# Swarm_Board_2.net
KiCad netlist of a schematic drawn in EAGLE
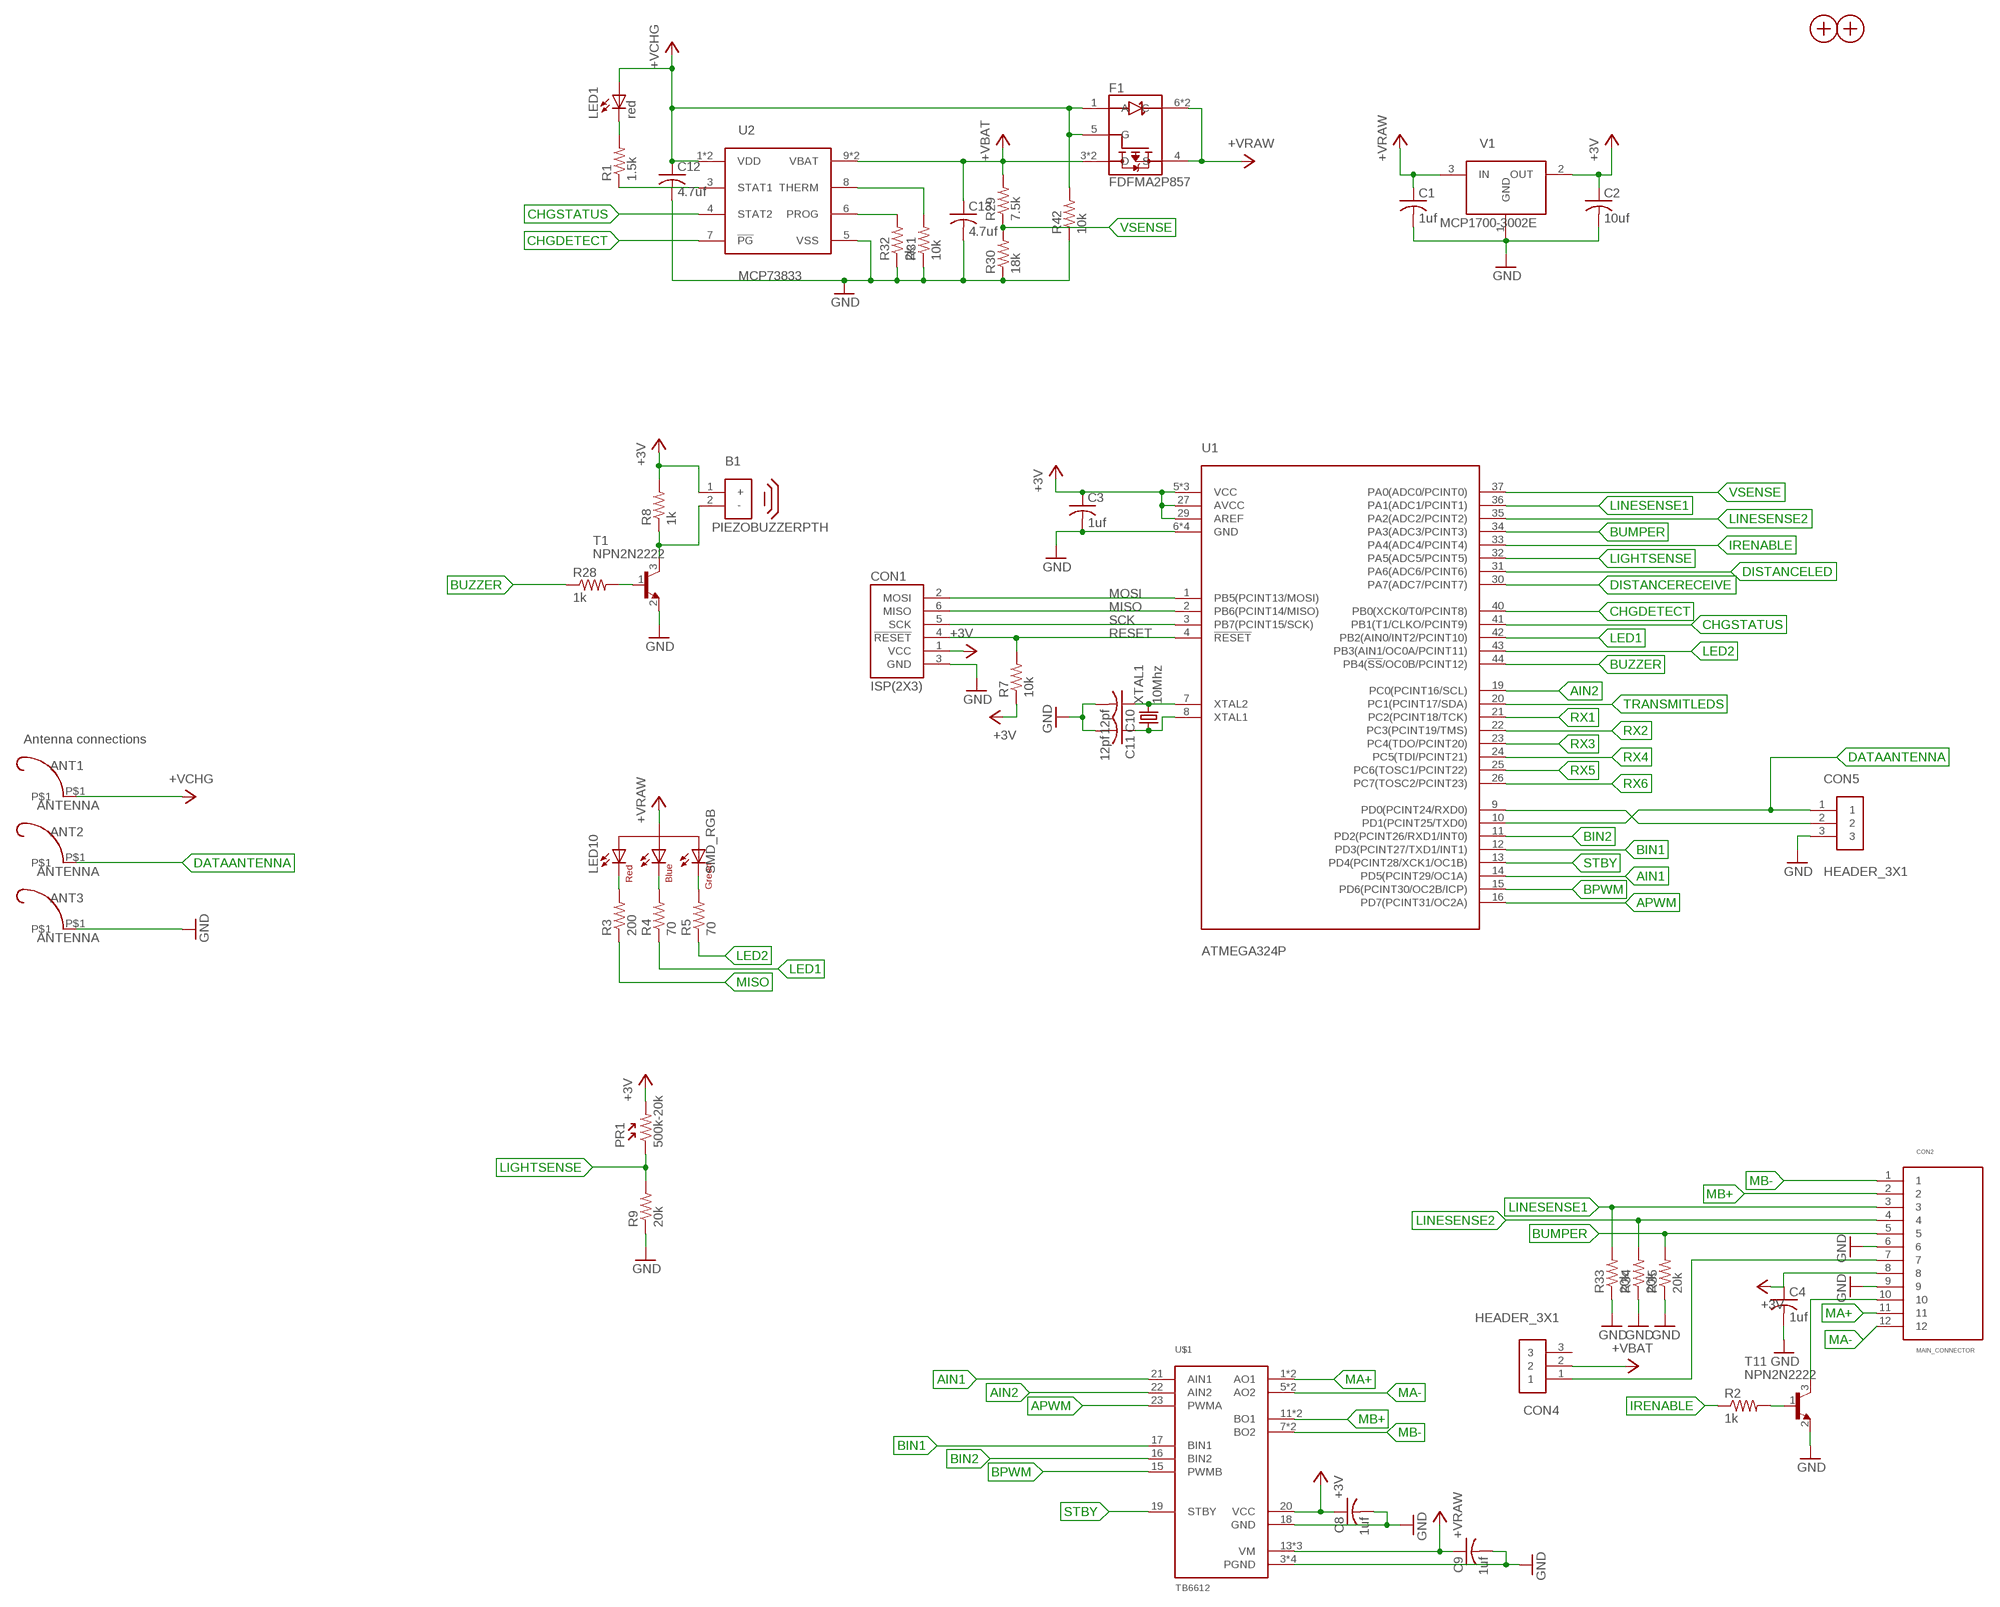
[diagram p0: schematic, sheet 1, part 1 of 2]
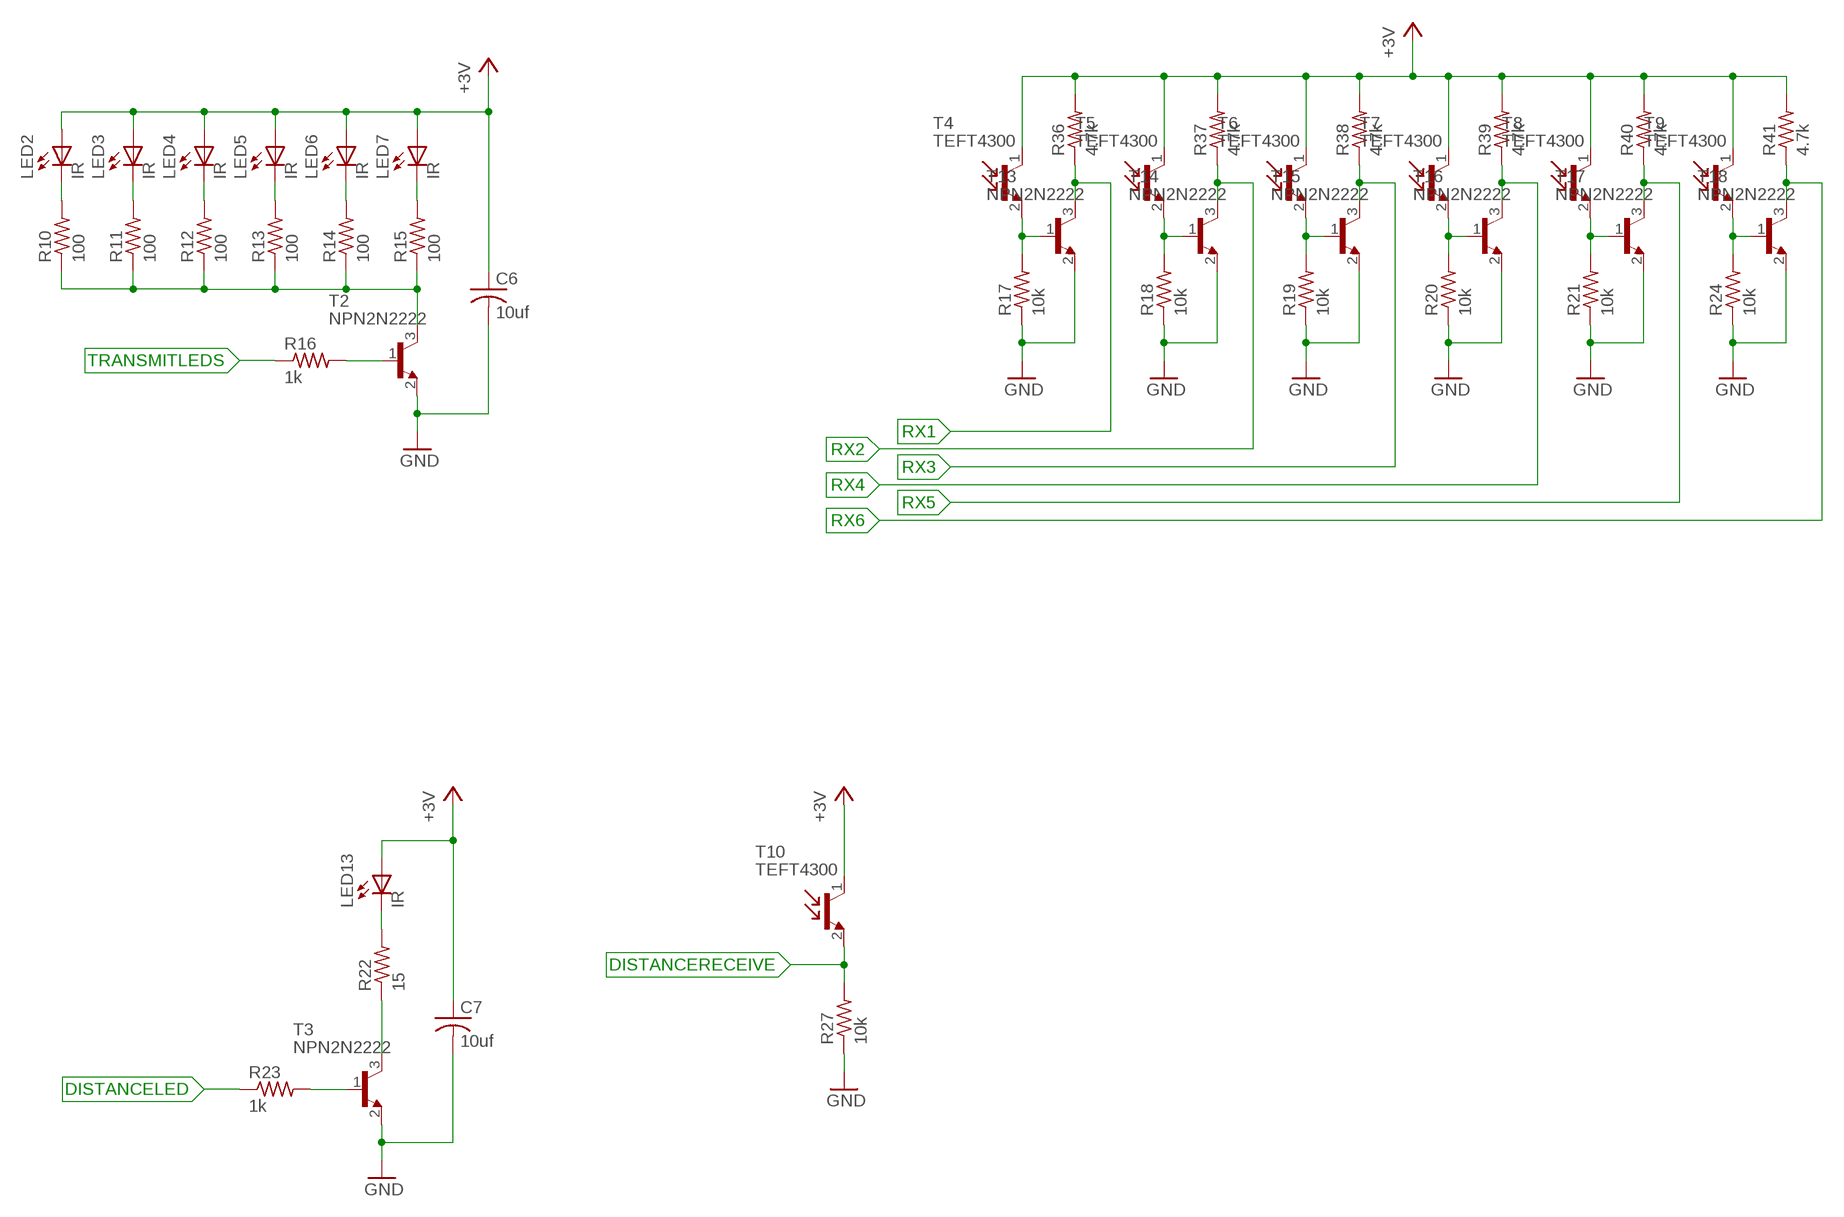
[diagram p1: schematic, sheet 1, part 2 of 2]

(export (version "E")
  (design (tool "Eeschema 10.0.6"))
  (components
    (comp (ref "ANT1")
      (value "ANTENNA")
      (footprint "eagle-import:ANTENNA")
      (libsource (lib "eagle-import") (part "ANTENNA"))
    )
    (comp (ref "ANT2")
      (value "ANTENNA")
      (footprint "eagle-import:ANTENNA")
      (libsource (lib "eagle-import") (part "ANTENNA"))
    )
    (comp (ref "ANT3")
      (value "ANTENNA")
      (footprint "eagle-import:ANTENNA")
      (libsource (lib "eagle-import") (part "ANTENNA"))
    )
    (comp (ref "B1")
      (value "PIEZOBUZZERPTH")
      (footprint "eagle-import:PIEZOBUZZER")
      (libsource (lib "eagle-import") (part "PIEZOBUZZERPTH"))
    )
    (comp (ref "C1")
      (value "1uf")
      (footprint "eagle-import:0603")
      (libsource (lib "eagle-import") (part "CAP0603"))
    )
    (comp (ref "C2")
      (value "10uf")
      (footprint "eagle-import:0805")
      (libsource (lib "eagle-import") (part "CAP0805"))
    )
    (comp (ref "C3")
      (value "1uf")
      (footprint "eagle-import:0603")
      (libsource (lib "eagle-import") (part "CAP0603"))
    )
    (comp (ref "C4")
      (value "1uf")
      (footprint "eagle-import:0603")
      (libsource (lib "eagle-import") (part "CAP0603"))
    )
    (comp (ref "C6")
      (value "10uf")
      (footprint "eagle-import:0805")
      (libsource (lib "eagle-import") (part "CAP0805"))
    )
    (comp (ref "C7")
      (value "10uf")
      (footprint "eagle-import:0805")
      (libsource (lib "eagle-import") (part "CAP0805"))
    )
    (comp (ref "C8")
      (value "1uf")
      (footprint "eagle-import:0603")
      (libsource (lib "eagle-import") (part "CAP0603"))
    )
    (comp (ref "C9")
      (value "1uf")
      (footprint "eagle-import:0603")
      (libsource (lib "eagle-import") (part "CAP0603"))
    )
    (comp (ref "C10")
      (value "12pf")
      (footprint "eagle-import:0603")
      (libsource (lib "eagle-import") (part "CAP0603"))
    )
    (comp (ref "C11")
      (value "12pf")
      (footprint "eagle-import:0603")
      (libsource (lib "eagle-import") (part "CAP0603"))
    )
    (comp (ref "C12")
      (value "4.7uf")
      (footprint "eagle-import:0603")
      (libsource (lib "eagle-import") (part "CAP0603"))
    )
    (comp (ref "C13")
      (value "4.7uf")
      (footprint "eagle-import:0603")
      (libsource (lib "eagle-import") (part "CAP0603"))
    )
    (comp (ref "CON1")
      (value "ISP(2X3)")
      (footprint "eagle-import:PINHEADER(2X3)")
      (libsource (lib "eagle-import") (part "ISP(2X3)"))
    )
    (comp (ref "CON2")
      (value "MAIN_CONNECTOR")
      (footprint "eagle-import:FEMALE_HEADER_2MM_2X6")
      (libsource (lib "eagle-import") (part "MAIN_CONNECTOR"))
    )
    (comp (ref "CON4")
      (value "HEADER_3X1")
      (footprint "eagle-import:3PINHEADER_.100_")
      (libsource (lib "eagle-import") (part "HEADER_3X1"))
    )
    (comp (ref "CON5")
      (value "HEADER_3X1")
      (footprint "eagle-import:3PINHEADER_.100_")
      (libsource (lib "eagle-import") (part "HEADER_3X1"))
    )
    (comp (ref "F1")
      (value "FDFMA2P857")
      (footprint "eagle-import:MICROFET2X2MM")
      (libsource (lib "eagle-import") (part "FDFMA2P857"))
    )
    (comp (ref "H1")
      (value "MOUNTINGHOLE")
      (footprint "eagle-import:MOUNTINGHOLE")
      (libsource (lib "eagle-import") (part "MOUNTINGHOLE"))
    )
    (comp (ref "H2")
      (value "MOUNTINGHOLE")
      (footprint "eagle-import:MOUNTINGHOLE")
      (libsource (lib "eagle-import") (part "MOUNTINGHOLE"))
    )
    (comp (ref "LED1")
      (value "red")
      (footprint "eagle-import:LED0603")
      (libsource (lib "eagle-import") (part "LED0603"))
    )
    (comp (ref "LED2")
      (value "IR")
      (footprint "eagle-import:5MM_LED_RA")
      (libsource (lib "eagle-import") (part "LED5MMRA"))
    )
    (comp (ref "LED3")
      (value "IR")
      (footprint "eagle-import:5MM_LED_RA")
      (libsource (lib "eagle-import") (part "LED5MMRA"))
    )
    (comp (ref "LED4")
      (value "IR")
      (footprint "eagle-import:5MM_LED_RA")
      (libsource (lib "eagle-import") (part "LED5MMRA"))
    )
    (comp (ref "LED5")
      (value "IR")
      (footprint "eagle-import:5MM_LED_RA")
      (libsource (lib "eagle-import") (part "LED5MMRA"))
    )
    (comp (ref "LED6")
      (value "IR")
      (footprint "eagle-import:5MM_LED_RA")
      (libsource (lib "eagle-import") (part "LED5MMRA"))
    )
    (comp (ref "LED7")
      (value "IR")
      (footprint "eagle-import:5MM_LED_RA")
      (libsource (lib "eagle-import") (part "LED5MMRA"))
    )
    (comp (ref "LED10")
      (value "SMD_RGB")
      (footprint "eagle-import:PLCC4")
      (libsource (lib "eagle-import") (part "SMD_RGB"))
    )
    (comp (ref "LED13")
      (value "IR")
      (footprint "eagle-import:5MM_LED_RA")
      (libsource (lib "eagle-import") (part "LED5MMRA"))
    )
    (comp (ref "PR1")
      (value "500k-20k")
      (footprint "eagle-import:CDSPHOTOCELL")
      (libsource (lib "eagle-import") (part "CDSPHOTORESISTOR"))
    )
    (comp (ref "R1")
      (value "1.5k")
      (footprint "eagle-import:0603")
      (libsource (lib "eagle-import") (part "RES0603"))
    )
    (comp (ref "R2")
      (value "1k")
      (footprint "eagle-import:0603")
      (libsource (lib "eagle-import") (part "RES0603"))
    )
    (comp (ref "R3")
      (value "200")
      (footprint "eagle-import:0603")
      (libsource (lib "eagle-import") (part "RES0603"))
    )
    (comp (ref "R4")
      (value "70")
      (footprint "eagle-import:0603")
      (libsource (lib "eagle-import") (part "RES0603"))
    )
    (comp (ref "R5")
      (value "70")
      (footprint "eagle-import:0603")
      (libsource (lib "eagle-import") (part "RES0603"))
    )
    (comp (ref "R7")
      (value "10k")
      (footprint "eagle-import:0603")
      (libsource (lib "eagle-import") (part "RES0603"))
    )
    (comp (ref "R8")
      (value "1k")
      (footprint "eagle-import:0603")
      (libsource (lib "eagle-import") (part "RES0603"))
    )
    (comp (ref "R9")
      (value "20k")
      (footprint "eagle-import:0603")
      (libsource (lib "eagle-import") (part "RES0603"))
    )
    (comp (ref "R10")
      (value "100")
      (footprint "eagle-import:0603")
      (libsource (lib "eagle-import") (part "RES0603"))
    )
    (comp (ref "R11")
      (value "100")
      (footprint "eagle-import:0603")
      (libsource (lib "eagle-import") (part "RES0603"))
    )
    (comp (ref "R12")
      (value "100")
      (footprint "eagle-import:0603")
      (libsource (lib "eagle-import") (part "RES0603"))
    )
    (comp (ref "R13")
      (value "100")
      (footprint "eagle-import:0603")
      (libsource (lib "eagle-import") (part "RES0603"))
    )
    (comp (ref "R14")
      (value "100")
      (footprint "eagle-import:0603")
      (libsource (lib "eagle-import") (part "RES0603"))
    )
    (comp (ref "R15")
      (value "100")
      (footprint "eagle-import:0603")
      (libsource (lib "eagle-import") (part "RES0603"))
    )
    (comp (ref "R16")
      (value "1k")
      (footprint "eagle-import:0603")
      (libsource (lib "eagle-import") (part "RES0603"))
    )
    (comp (ref "R17")
      (value "10k")
      (footprint "eagle-import:0603")
      (libsource (lib "eagle-import") (part "RES0603"))
    )
    (comp (ref "R18")
      (value "10k")
      (footprint "eagle-import:0603")
      (libsource (lib "eagle-import") (part "RES0603"))
    )
    (comp (ref "R19")
      (value "10k")
      (footprint "eagle-import:0603")
      (libsource (lib "eagle-import") (part "RES0603"))
    )
    (comp (ref "R20")
      (value "10k")
      (footprint "eagle-import:0603")
      (libsource (lib "eagle-import") (part "RES0603"))
    )
    (comp (ref "R21")
      (value "10k")
      (footprint "eagle-import:0603")
      (libsource (lib "eagle-import") (part "RES0603"))
    )
    (comp (ref "R22")
      (value "15")
      (footprint "eagle-import:0603")
      (libsource (lib "eagle-import") (part "RES0603"))
    )
    (comp (ref "R23")
      (value "1k")
      (footprint "eagle-import:0603")
      (libsource (lib "eagle-import") (part "RES0603"))
    )
    (comp (ref "R24")
      (value "10k")
      (footprint "eagle-import:0603")
      (libsource (lib "eagle-import") (part "RES0603"))
    )
    (comp (ref "R27")
      (value "10k")
      (footprint "eagle-import:0603")
      (libsource (lib "eagle-import") (part "RES0603"))
    )
    (comp (ref "R28")
      (value "1k")
      (footprint "eagle-import:0603")
      (libsource (lib "eagle-import") (part "RES0603"))
    )
    (comp (ref "R29")
      (value "7.5k")
      (footprint "eagle-import:0603")
      (libsource (lib "eagle-import") (part "RES0603"))
    )
    (comp (ref "R30")
      (value "18k")
      (footprint "eagle-import:0603")
      (libsource (lib "eagle-import") (part "RES0603"))
    )
    (comp (ref "R31")
      (value "10k")
      (footprint "eagle-import:0603")
      (libsource (lib "eagle-import") (part "RES0603"))
    )
    (comp (ref "R32")
      (value "2k")
      (footprint "eagle-import:0603")
      (libsource (lib "eagle-import") (part "RES0603"))
    )
    (comp (ref "R33")
      (value "20k")
      (footprint "eagle-import:0603")
      (libsource (lib "eagle-import") (part "RES0603"))
    )
    (comp (ref "R34")
      (value "20k")
      (footprint "eagle-import:0603")
      (libsource (lib "eagle-import") (part "RES0603"))
    )
    (comp (ref "R35")
      (value "20k")
      (footprint "eagle-import:0603")
      (libsource (lib "eagle-import") (part "RES0603"))
    )
    (comp (ref "R36")
      (value "4.7k")
      (footprint "eagle-import:0603")
      (libsource (lib "eagle-import") (part "RES0603"))
    )
    (comp (ref "R37")
      (value "4.7k")
      (footprint "eagle-import:0603")
      (libsource (lib "eagle-import") (part "RES0603"))
    )
    (comp (ref "R38")
      (value "4.7k")
      (footprint "eagle-import:0603")
      (libsource (lib "eagle-import") (part "RES0603"))
    )
    (comp (ref "R39")
      (value "4.7k")
      (footprint "eagle-import:0603")
      (libsource (lib "eagle-import") (part "RES0603"))
    )
    (comp (ref "R40")
      (value "4.7k")
      (footprint "eagle-import:0603")
      (libsource (lib "eagle-import") (part "RES0603"))
    )
    (comp (ref "R41")
      (value "4.7k")
      (footprint "eagle-import:0603")
      (libsource (lib "eagle-import") (part "RES0603"))
    )
    (comp (ref "R42")
      (value "10k")
      (footprint "eagle-import:0603")
      (libsource (lib "eagle-import") (part "RES0603"))
    )
    (comp (ref "T1")
      (value "NPN2N2222")
      (footprint "eagle-import:SOT23")
      (libsource (lib "eagle-import") (part "NPN2N2222"))
    )
    (comp (ref "T2")
      (value "NPN2N2222")
      (footprint "eagle-import:SOT23")
      (libsource (lib "eagle-import") (part "NPN2N2222"))
    )
    (comp (ref "T3")
      (value "NPN2N2222")
      (footprint "eagle-import:SOT23")
      (libsource (lib "eagle-import") (part "NPN2N2222"))
    )
    (comp (ref "T4")
      (value "TEFT4300")
      (footprint "eagle-import:3MM_LED_RA")
      (libsource (lib "eagle-import") (part "TEFT4300"))
    )
    (comp (ref "T5")
      (value "TEFT4300")
      (footprint "eagle-import:3MM_LED_RA")
      (libsource (lib "eagle-import") (part "TEFT4300"))
    )
    (comp (ref "T6")
      (value "TEFT4300")
      (footprint "eagle-import:3MM_LED_RA")
      (libsource (lib "eagle-import") (part "TEFT4300"))
    )
    (comp (ref "T7")
      (value "TEFT4300")
      (footprint "eagle-import:3MM_LED_RA")
      (libsource (lib "eagle-import") (part "TEFT4300"))
    )
    (comp (ref "T8")
      (value "TEFT4300")
      (footprint "eagle-import:3MM_LED_RA")
      (libsource (lib "eagle-import") (part "TEFT4300"))
    )
    (comp (ref "T9")
      (value "TEFT4300")
      (footprint "eagle-import:3MM_LED_RA")
      (libsource (lib "eagle-import") (part "TEFT4300"))
    )
    (comp (ref "T10")
      (value "TEFT4300")
      (footprint "eagle-import:3MM_LED_RA")
      (libsource (lib "eagle-import") (part "TEFT4300"))
    )
    (comp (ref "T11")
      (value "NPN2N2222")
      (footprint "eagle-import:SOT23")
      (libsource (lib "eagle-import") (part "NPN2N2222"))
    )
    (comp (ref "T13")
      (value "NPN2N2222")
      (footprint "eagle-import:SOT23")
      (libsource (lib "eagle-import") (part "NPN2N2222"))
    )
    (comp (ref "T14")
      (value "NPN2N2222")
      (footprint "eagle-import:SOT23")
      (libsource (lib "eagle-import") (part "NPN2N2222"))
    )
    (comp (ref "T15")
      (value "NPN2N2222")
      (footprint "eagle-import:SOT23")
      (libsource (lib "eagle-import") (part "NPN2N2222"))
    )
    (comp (ref "T16")
      (value "NPN2N2222")
      (footprint "eagle-import:SOT23")
      (libsource (lib "eagle-import") (part "NPN2N2222"))
    )
    (comp (ref "T17")
      (value "NPN2N2222")
      (footprint "eagle-import:SOT23")
      (libsource (lib "eagle-import") (part "NPN2N2222"))
    )
    (comp (ref "T18")
      (value "NPN2N2222")
      (footprint "eagle-import:SOT23")
      (libsource (lib "eagle-import") (part "NPN2N2222"))
    )
    (comp (ref "U$1")
      (value "TB6612")
      (footprint "eagle-import:24SSOP")
      (libsource (lib "eagle-import") (part "TB6612"))
    )
    (comp (ref "U1")
      (value "ATMEGA324P")
      (footprint "eagle-import:TQFP44")
      (libsource (lib "eagle-import") (part "ATMEGA324P"))
    )
    (comp (ref "U2")
      (value "MCP73833")
      (footprint "eagle-import:MSOP10")
      (libsource (lib "eagle-import") (part "MCP73833"))
    )
    (comp (ref "V1")
      (value "MCP1700-3002E")
      (footprint "eagle-import:(TT_NB)SOT-23(3PAD)")
      (libsource (lib "eagle-import") (part "MCP1700-3002E"))
    )
    (comp (ref "XTAL1")
      (value "10Mhz")
      (footprint "eagle-import:SMDXTAL")
      (libsource (lib "eagle-import") (part "NX5032GA-10.000000MHZ"))
    )
  )
  (nets
    (net (code "1") (name "+3V") (class "Default")
      (node (ref "B1") (pin "1") (pinfunction "+_1") (pintype "bidirectional"))
      (node (ref "C2") (pin "1") (pinfunction "1_1") (pintype "passive"))
      (node (ref "C3") (pin "1") (pinfunction "1_1") (pintype "passive"))
      (node (ref "C4") (pin "1") (pinfunction "1_1") (pintype "passive"))
      (node (ref "C6") (pin "1") (pinfunction "1_1") (pintype "passive"))
      (node (ref "C7") (pin "1") (pinfunction "1_1") (pintype "passive"))
      (node (ref "C8") (pin "1") (pinfunction "1_1") (pintype "passive"))
      (node (ref "CON1") (pin "1") (pinfunction "VCC_1") (pintype "bidirectional"))
      (node (ref "CON2") (pin "8") (pinfunction "8_8") (pintype "bidirectional"))
      (node (ref "LED13") (pin "1") (pinfunction "A_1") (pintype "passive"))
      (node (ref "LED2") (pin "1") (pinfunction "A_1") (pintype "passive"))
      (node (ref "LED3") (pin "1") (pinfunction "A_1") (pintype "passive"))
      (node (ref "LED4") (pin "1") (pinfunction "A_1") (pintype "passive"))
      (node (ref "LED5") (pin "1") (pinfunction "A_1") (pintype "passive"))
      (node (ref "LED6") (pin "1") (pinfunction "A_1") (pintype "passive"))
      (node (ref "LED7") (pin "1") (pinfunction "A_1") (pintype "passive"))
      (node (ref "PR1") (pin "2") (pinfunction "2_2") (pintype "passive"))
      (node (ref "R36") (pin "2") (pinfunction "2_2") (pintype "passive"))
      (node (ref "R37") (pin "2") (pinfunction "2_2") (pintype "passive"))
      (node (ref "R38") (pin "2") (pinfunction "2_2") (pintype "passive"))
      (node (ref "R39") (pin "2") (pinfunction "2_2") (pintype "passive"))
      (node (ref "R40") (pin "2") (pinfunction "2_2") (pintype "passive"))
      (node (ref "R41") (pin "2") (pinfunction "2_2") (pintype "passive"))
      (node (ref "R7") (pin "1") (pinfunction "1_1") (pintype "passive"))
      (node (ref "R8") (pin "2") (pinfunction "2_2") (pintype "passive"))
      (node (ref "T10") (pin "1") (pinfunction "C_1") (pintype "passive"))
      (node (ref "T4") (pin "1") (pinfunction "C_1") (pintype "passive"))
      (node (ref "T5") (pin "1") (pinfunction "C_1") (pintype "passive"))
      (node (ref "T6") (pin "1") (pinfunction "C_1") (pintype "passive"))
      (node (ref "T7") (pin "1") (pinfunction "C_1") (pintype "passive"))
      (node (ref "T8") (pin "1") (pinfunction "C_1") (pintype "passive"))
      (node (ref "T9") (pin "1") (pinfunction "C_1") (pintype "passive"))
      (node (ref "U$1") (pin "20") (pinfunction "VCC_20") (pintype "bidirectional"))
      (node (ref "U1") (pin "17") (pinfunction "VCC_17") (pintype "bidirectional"))
      (node (ref "U1") (pin "27") (pinfunction "AVCC_27") (pintype "bidirectional"))
      (node (ref "U1") (pin "29") (pinfunction "AREF_29") (pintype "bidirectional"))
      (node (ref "U1") (pin "38") (pinfunction "VCC_38") (pintype "bidirectional"))
      (node (ref "U1") (pin "5") (pinfunction "VCC_5") (pintype "bidirectional"))
      (node (ref "V1") (pin "2") (pinfunction "OUT_2") (pintype "bidirectional"))
    )
    (net (code "2") (name "+VBAT") (class "Default")
      (node (ref "C13") (pin "1") (pinfunction "1_1") (pintype "passive"))
      (node (ref "CON4") (pin "2") (pinfunction "2_2") (pintype "bidirectional"))
      (node (ref "F1") (pin "3") (pinfunction "D_3") (pintype "bidirectional"))
      (node (ref "F1") (pin "8") (pinfunction "D_8") (pintype "bidirectional"))
      (node (ref "R29") (pin "2") (pinfunction "2_2") (pintype "passive"))
      (node (ref "U2") (pin "10") (pinfunction "VBAT_10") (pintype "bidirectional"))
      (node (ref "U2") (pin "9") (pinfunction "VBAT_9") (pintype "bidirectional"))
    )
    (net (code "3") (name "+VCHG") (class "Default")
      (node (ref "ANT1") (pin "P$1") (pinfunction "P$1_P$1") (pintype "bidirectional"))
      (node (ref "C12") (pin "1") (pinfunction "1_1") (pintype "passive"))
      (node (ref "F1") (pin "1") (pinfunction "A_1") (pintype "bidirectional"))
      (node (ref "F1") (pin "5") (pinfunction "G_5") (pintype "bidirectional"))
      (node (ref "LED1") (pin "2") (pinfunction "A_2") (pintype "passive"))
      (node (ref "R42") (pin "2") (pinfunction "2_2") (pintype "passive"))
      (node (ref "U2") (pin "1") (pinfunction "VDD_1") (pintype "bidirectional"))
      (node (ref "U2") (pin "2") (pinfunction "VDD_2") (pintype "bidirectional"))
    )
    (net (code "4") (name "+VRAW") (class "Default")
      (node (ref "C1") (pin "1") (pinfunction "1_1") (pintype "passive"))
      (node (ref "C9") (pin "1") (pinfunction "1_1") (pintype "passive"))
      (node (ref "F1") (pin "4") (pinfunction "S_4") (pintype "bidirectional"))
      (node (ref "F1") (pin "6") (pinfunction "C_6") (pintype "bidirectional"))
      (node (ref "F1") (pin "7") (pinfunction "C_7") (pintype "bidirectional"))
      (node (ref "LED10") (pin "2") (pinfunction "COMMONANODE_2") (pintype "passive"))
      (node (ref "U$1") (pin "13") (pinfunction "VM_13") (pintype "bidirectional"))
      (node (ref "U$1") (pin "14") (pinfunction "VM_14") (pintype "bidirectional"))
      (node (ref "U$1") (pin "24") (pinfunction "VM_24") (pintype "bidirectional"))
      (node (ref "V1") (pin "3") (pinfunction "IN_3") (pintype "bidirectional"))
    )
    (net (code "5") (name "/MOSI") (class "Default")
      (node (ref "CON1") (pin "2") (pinfunction "MOSI_2") (pintype "bidirectional"))
      (node (ref "U1") (pin "1") (pinfunction "PB5(PCINT13/MOSI)_1") (pintype "bidirectional"))
    )
    (net (code "6") (name "/RESET") (class "Default")
      (node (ref "CON1") (pin "4") (pinfunction "~{RESET}_4") (pintype "bidirectional"))
      (node (ref "R7") (pin "2") (pinfunction "2_2") (pintype "passive"))
      (node (ref "U1") (pin "4") (pinfunction "~{RESET}_4") (pintype "bidirectional"))
    )
    (net (code "7") (name "/SCK") (class "Default")
      (node (ref "CON1") (pin "5") (pinfunction "SCK_5") (pintype "bidirectional"))
      (node (ref "U1") (pin "3") (pinfunction "PB7(PCINT15/SCK)_3") (pintype "bidirectional"))
    )
    (net (code "8") (name "AIN1") (class "Default")
      (node (ref "U$1") (pin "21") (pinfunction "AIN1_21") (pintype "bidirectional"))
      (node (ref "U1") (pin "14") (pinfunction "PD5(PCINT29/OC1A)_14") (pintype "bidirectional"))
    )
    (net (code "9") (name "AIN2") (class "Default")
      (node (ref "U$1") (pin "22") (pinfunction "AIN2_22") (pintype "bidirectional"))
      (node (ref "U1") (pin "19") (pinfunction "PC0(PCINT16/SCL)_19") (pintype "bidirectional"))
    )
    (net (code "10") (name "APWM") (class "Default")
      (node (ref "U$1") (pin "23") (pinfunction "PWMA_23") (pintype "bidirectional"))
      (node (ref "U1") (pin "16") (pinfunction "PD7(PCINT31/OC2A)_16") (pintype "bidirectional"))
    )
    (net (code "11") (name "BIN1") (class "Default")
      (node (ref "U$1") (pin "17") (pinfunction "BIN1_17") (pintype "bidirectional"))
      (node (ref "U1") (pin "12") (pinfunction "PD3(PCINT27/TXD1/INT1)_12") (pintype "bidirectional"))
    )
    (net (code "12") (name "BIN2") (class "Default")
      (node (ref "U$1") (pin "16") (pinfunction "BIN2_16") (pintype "bidirectional"))
      (node (ref "U1") (pin "11") (pinfunction "PD2(PCINT26/RXD1/INT0)_11") (pintype "bidirectional"))
    )
    (net (code "13") (name "BPWM") (class "Default")
      (node (ref "U$1") (pin "15") (pinfunction "PWMB_15") (pintype "bidirectional"))
      (node (ref "U1") (pin "15") (pinfunction "PD6(PCINT30/OC2B/ICP)_15") (pintype "bidirectional"))
    )
    (net (code "14") (name "BUMPER") (class "Default")
      (node (ref "CON2") (pin "5") (pinfunction "5_5") (pintype "bidirectional"))
      (node (ref "R35") (pin "2") (pinfunction "2_2") (pintype "passive"))
      (node (ref "U1") (pin "34") (pinfunction "PA3(ADC3/PCINT3)_34") (pintype "bidirectional"))
    )
    (net (code "15") (name "BUZZER") (class "Default")
      (node (ref "R28") (pin "1") (pinfunction "1_1") (pintype "passive"))
      (node (ref "U1") (pin "44") (pinfunction "PB4(~{SS}/OC0B/PCINT12)_44") (pintype "bidirectional"))
    )
    (net (code "16") (name "CHGDETECT") (class "Default")
      (node (ref "U1") (pin "40") (pinfunction "PB0(XCK0/T0/PCINT8)_40") (pintype "bidirectional"))
      (node (ref "U2") (pin "7") (pinfunction "~{PG}_7") (pintype "bidirectional"))
    )
    (net (code "17") (name "CHGSTATUS") (class "Default")
      (node (ref "U1") (pin "41") (pinfunction "PB1(T1/CLKO/PCINT9)_41") (pintype "bidirectional"))
      (node (ref "U2") (pin "4") (pinfunction "STAT2_4") (pintype "bidirectional"))
    )
    (net (code "18") (name "DATAANTENNA") (class "Default")
      (node (ref "ANT2") (pin "P$1") (pinfunction "P$1_P$1") (pintype "bidirectional"))
      (node (ref "CON5") (pin "1") (pinfunction "1_1") (pintype "bidirectional"))
      (node (ref "U1") (pin "10") (pinfunction "PD1(PCINT25/TXD0)_10") (pintype "bidirectional"))
    )
    (net (code "19") (name "DISTANCELED") (class "Default")
      (node (ref "R23") (pin "1") (pinfunction "1_1") (pintype "passive"))
      (node (ref "U1") (pin "31") (pinfunction "PA6(ADC6/PCINT6)_31") (pintype "bidirectional"))
    )
    (net (code "20") (name "DISTANCERECEIVE") (class "Default")
      (node (ref "R27") (pin "2") (pinfunction "2_2") (pintype "passive"))
      (node (ref "T10") (pin "2") (pinfunction "E_2") (pintype "passive"))
      (node (ref "U1") (pin "30") (pinfunction "PA7(ADC7/PCINT7)_30") (pintype "bidirectional"))
    )
    (net (code "21") (name "GND") (class "Default")
      (node (ref "ANT3") (pin "P$1") (pinfunction "P$1_P$1") (pintype "bidirectional"))
      (node (ref "C1") (pin "2") (pinfunction "2_2") (pintype "passive"))
      (node (ref "C10") (pin "2") (pinfunction "2_2") (pintype "passive"))
      (node (ref "C11") (pin "2") (pinfunction "2_2") (pintype "passive"))
      (node (ref "C12") (pin "2") (pinfunction "2_2") (pintype "passive"))
      (node (ref "C13") (pin "2") (pinfunction "2_2") (pintype "passive"))
      (node (ref "C2") (pin "2") (pinfunction "2_2") (pintype "passive"))
      (node (ref "C3") (pin "2") (pinfunction "2_2") (pintype "passive"))
      (node (ref "C4") (pin "2") (pinfunction "2_2") (pintype "passive"))
      (node (ref "C6") (pin "2") (pinfunction "2_2") (pintype "passive"))
      (node (ref "C7") (pin "2") (pinfunction "2_2") (pintype "passive"))
      (node (ref "C8") (pin "2") (pinfunction "2_2") (pintype "passive"))
      (node (ref "C9") (pin "2") (pinfunction "2_2") (pintype "passive"))
      (node (ref "CON1") (pin "3") (pinfunction "GND_3") (pintype "bidirectional"))
      (node (ref "CON2") (pin "6") (pinfunction "6_6") (pintype "bidirectional"))
      (node (ref "CON2") (pin "9") (pinfunction "9_9") (pintype "bidirectional"))
      (node (ref "CON5") (pin "3") (pinfunction "3_3") (pintype "bidirectional"))
      (node (ref "R17") (pin "1") (pinfunction "1_1") (pintype "passive"))
      (node (ref "R18") (pin "1") (pinfunction "1_1") (pintype "passive"))
      (node (ref "R19") (pin "1") (pinfunction "1_1") (pintype "passive"))
      (node (ref "R20") (pin "1") (pinfunction "1_1") (pintype "passive"))
      (node (ref "R21") (pin "1") (pinfunction "1_1") (pintype "passive"))
      (node (ref "R24") (pin "1") (pinfunction "1_1") (pintype "passive"))
      (node (ref "R27") (pin "1") (pinfunction "1_1") (pintype "passive"))
      (node (ref "R30") (pin "1") (pinfunction "1_1") (pintype "passive"))
      (node (ref "R31") (pin "1") (pinfunction "1_1") (pintype "passive"))
      (node (ref "R32") (pin "1") (pinfunction "1_1") (pintype "passive"))
      (node (ref "R33") (pin "1") (pinfunction "1_1") (pintype "passive"))
      (node (ref "R34") (pin "1") (pinfunction "1_1") (pintype "passive"))
      (node (ref "R35") (pin "1") (pinfunction "1_1") (pintype "passive"))
      (node (ref "R42") (pin "1") (pinfunction "1_1") (pintype "passive"))
      (node (ref "R9") (pin "1") (pinfunction "1_1") (pintype "passive"))
      (node (ref "T1") (pin "2") (pinfunction "E_2") (pintype "passive"))
      (node (ref "T11") (pin "2") (pinfunction "E_2") (pintype "passive"))
      (node (ref "T13") (pin "2") (pinfunction "E_2") (pintype "passive"))
      (node (ref "T14") (pin "2") (pinfunction "E_2") (pintype "passive"))
      (node (ref "T15") (pin "2") (pinfunction "E_2") (pintype "passive"))
      (node (ref "T16") (pin "2") (pinfunction "E_2") (pintype "passive"))
      (node (ref "T17") (pin "2") (pinfunction "E_2") (pintype "passive"))
      (node (ref "T18") (pin "2") (pinfunction "E_2") (pintype "passive"))
      (node (ref "T2") (pin "2") (pinfunction "E_2") (pintype "passive"))
      (node (ref "T3") (pin "2") (pinfunction "E_2") (pintype "passive"))
      (node (ref "U$1") (pin "10") (pinfunction "PGND_10") (pintype "bidirectional"))
      (node (ref "U$1") (pin "18") (pinfunction "GND_18") (pintype "bidirectional"))
      (node (ref "U$1") (pin "3") (pinfunction "PGND_3") (pintype "bidirectional"))
      (node (ref "U$1") (pin "4") (pinfunction "PGND_4") (pintype "bidirectional"))
      (node (ref "U$1") (pin "9") (pinfunction "PGND_9") (pintype "bidirectional"))
      (node (ref "U1") (pin "18") (pinfunction "GND_18") (pintype "bidirectional"))
      (node (ref "U1") (pin "28") (pinfunction "GND_28") (pintype "bidirectional"))
      (node (ref "U1") (pin "39") (pinfunction "GND_39") (pintype "bidirectional"))
      (node (ref "U1") (pin "6") (pinfunction "GND_6") (pintype "bidirectional"))
      (node (ref "U2") (pin "5") (pinfunction "VSS_5") (pintype "bidirectional"))
      (node (ref "V1") (pin "1") (pinfunction "GND_1") (pintype "bidirectional"))
    )
    (net (code "22") (name "IRENABLE") (class "Default")
      (node (ref "R2") (pin "1") (pinfunction "1_1") (pintype "passive"))
      (node (ref "U1") (pin "33") (pinfunction "PA4(ADC4/PCINT4)_33") (pintype "bidirectional"))
    )
    (net (code "23") (name "LED1") (class "Default")
      (node (ref "R4") (pin "1") (pinfunction "1_1") (pintype "passive"))
      (node (ref "U1") (pin "42") (pinfunction "PB2(AIN0/INT2/PCINT10)_42") (pintype "bidirectional"))
    )
    (net (code "24") (name "LED2") (class "Default")
      (node (ref "R5") (pin "1") (pinfunction "1_1") (pintype "passive"))
      (node (ref "U1") (pin "43") (pinfunction "PB3(AIN1/OC0A/PCINT11)_43") (pintype "bidirectional"))
    )
    (net (code "25") (name "LIGHTSENSE") (class "Default")
      (node (ref "PR1") (pin "1") (pinfunction "1_1") (pintype "passive"))
      (node (ref "R9") (pin "2") (pinfunction "2_2") (pintype "passive"))
      (node (ref "U1") (pin "32") (pinfunction "PA5(ADC5/PCINT5)_32") (pintype "bidirectional"))
    )
    (net (code "26") (name "LINESENSE1") (class "Default")
      (node (ref "CON2") (pin "3") (pinfunction "3_3") (pintype "bidirectional"))
      (node (ref "R33") (pin "2") (pinfunction "2_2") (pintype "passive"))
      (node (ref "U1") (pin "36") (pinfunction "PA1(ADC1/PCINT1)_36") (pintype "bidirectional"))
    )
    (net (code "27") (name "LINESENSE2") (class "Default")
      (node (ref "CON2") (pin "4") (pinfunction "4_4") (pintype "bidirectional"))
      (node (ref "R34") (pin "2") (pinfunction "2_2") (pintype "passive"))
      (node (ref "U1") (pin "35") (pinfunction "PA2(ADC2/PCINT2)_35") (pintype "bidirectional"))
    )
    (net (code "28") (name "MA+") (class "Default")
      (node (ref "CON2") (pin "11") (pinfunction "11_11") (pintype "bidirectional"))
      (node (ref "U$1") (pin "1") (pinfunction "AO1_1") (pintype "bidirectional"))
      (node (ref "U$1") (pin "2") (pinfunction "AO1_2") (pintype "bidirectional"))
    )
    (net (code "29") (name "MA-") (class "Default")
      (node (ref "CON2") (pin "12") (pinfunction "12_12") (pintype "bidirectional"))
      (node (ref "U$1") (pin "5") (pinfunction "AO2_5") (pintype "bidirectional"))
      (node (ref "U$1") (pin "6") (pinfunction "AO2_6") (pintype "bidirectional"))
    )
    (net (code "30") (name "MB+") (class "Default")
      (node (ref "CON2") (pin "2") (pinfunction "2_2") (pintype "bidirectional"))
      (node (ref "U$1") (pin "11") (pinfunction "BO1_11") (pintype "bidirectional"))
      (node (ref "U$1") (pin "12") (pinfunction "BO1_12") (pintype "bidirectional"))
    )
    (net (code "31") (name "MB-") (class "Default")
      (node (ref "CON2") (pin "1") (pinfunction "1_1") (pintype "bidirectional"))
      (node (ref "U$1") (pin "7") (pinfunction "BO2_7") (pintype "bidirectional"))
      (node (ref "U$1") (pin "8") (pinfunction "BO2_8") (pintype "bidirectional"))
    )
    (net (code "32") (name "MISO") (class "Default")
      (node (ref "CON1") (pin "6") (pinfunction "MISO_6") (pintype "bidirectional"))
      (node (ref "R3") (pin "1") (pinfunction "1_1") (pintype "passive"))
      (node (ref "U1") (pin "2") (pinfunction "PB6(PCINT14/MISO)_2") (pintype "bidirectional"))
    )
    (net (code "33") (name "Net-(B1--)") (class "Default")
      (node (ref "B1") (pin "2") (pinfunction "-_2") (pintype "bidirectional"))
      (node (ref "R8") (pin "1") (pinfunction "1_1") (pintype "passive"))
      (node (ref "T1") (pin "3") (pinfunction "C_3") (pintype "passive"))
    )
    (net (code "34") (name "Net-(CON2-Pad7)") (class "Default")
      (node (ref "CON2") (pin "7") (pinfunction "7_7") (pintype "bidirectional"))
      (node (ref "CON4") (pin "1") (pinfunction "1_1") (pintype "bidirectional"))
    )
    (net (code "35") (name "Net-(LED1-C)") (class "Default")
      (node (ref "LED1") (pin "1") (pinfunction "C_1") (pintype "passive"))
      (node (ref "R1") (pin "2") (pinfunction "2_2") (pintype "passive"))
    )
    (net (code "36") (name "Net-(LED2-C)") (class "Default")
      (node (ref "LED2") (pin "2") (pinfunction "C_2") (pintype "passive"))
      (node (ref "R10") (pin "2") (pinfunction "2_2") (pintype "passive"))
    )
    (net (code "37") (name "Net-(LED3-C)") (class "Default")
      (node (ref "LED3") (pin "2") (pinfunction "C_2") (pintype "passive"))
      (node (ref "R11") (pin "2") (pinfunction "2_2") (pintype "passive"))
    )
    (net (code "38") (name "Net-(LED4-C)") (class "Default")
      (node (ref "LED4") (pin "2") (pinfunction "C_2") (pintype "passive"))
      (node (ref "R12") (pin "2") (pinfunction "2_2") (pintype "passive"))
    )
    (net (code "39") (name "Net-(LED5-C)") (class "Default")
      (node (ref "LED5") (pin "2") (pinfunction "C_2") (pintype "passive"))
      (node (ref "R13") (pin "2") (pinfunction "2_2") (pintype "passive"))
    )
    (net (code "40") (name "Net-(LED6-C)") (class "Default")
      (node (ref "LED6") (pin "2") (pinfunction "C_2") (pintype "passive"))
      (node (ref "R14") (pin "2") (pinfunction "2_2") (pintype "passive"))
    )
    (net (code "41") (name "Net-(LED7-C)") (class "Default")
      (node (ref "LED7") (pin "2") (pinfunction "C_2") (pintype "passive"))
      (node (ref "R15") (pin "2") (pinfunction "2_2") (pintype "passive"))
    )
    (net (code "42") (name "Net-(LED10-BLUECATHODE)") (class "Default")
      (node (ref "LED10") (pin "3") (pinfunction "BLUECATHODE_3") (pintype "passive"))
      (node (ref "R4") (pin "2") (pinfunction "2_2") (pintype "passive"))
    )
    (net (code "43") (name "Net-(LED10-GREENCATHODE)") (class "Default")
      (node (ref "LED10") (pin "4") (pinfunction "GREENCATHODE_4") (pintype "passive"))
      (node (ref "R5") (pin "2") (pinfunction "2_2") (pintype "passive"))
    )
    (net (code "44") (name "Net-(LED10-REDCATHODE)") (class "Default")
      (node (ref "LED10") (pin "1") (pinfunction "REDCATHODE_1") (pintype "passive"))
      (node (ref "R3") (pin "2") (pinfunction "2_2") (pintype "passive"))
    )
    (net (code "45") (name "Net-(LED13-C)") (class "Default")
      (node (ref "LED13") (pin "2") (pinfunction "C_2") (pintype "passive"))
      (node (ref "R22") (pin "2") (pinfunction "2_2") (pintype "passive"))
    )
    (net (code "46") (name "Net-(T1-B)") (class "Default")
      (node (ref "R28") (pin "2") (pinfunction "2_2") (pintype "passive"))
      (node (ref "T1") (pin "1") (pinfunction "B_1") (pintype "passive"))
    )
    (net (code "47") (name "Net-(T2-B)") (class "Default")
      (node (ref "R16") (pin "2") (pinfunction "2_2") (pintype "passive"))
      (node (ref "T2") (pin "1") (pinfunction "B_1") (pintype "passive"))
    )
    (net (code "48") (name "Net-(T2-C)") (class "Default")
      (node (ref "R10") (pin "1") (pinfunction "1_1") (pintype "passive"))
      (node (ref "R11") (pin "1") (pinfunction "1_1") (pintype "passive"))
      (node (ref "R12") (pin "1") (pinfunction "1_1") (pintype "passive"))
      (node (ref "R13") (pin "1") (pinfunction "1_1") (pintype "passive"))
      (node (ref "R14") (pin "1") (pinfunction "1_1") (pintype "passive"))
      (node (ref "R15") (pin "1") (pinfunction "1_1") (pintype "passive"))
      (node (ref "T2") (pin "3") (pinfunction "C_3") (pintype "passive"))
    )
    (net (code "49") (name "Net-(T3-B)") (class "Default")
      (node (ref "R23") (pin "2") (pinfunction "2_2") (pintype "passive"))
      (node (ref "T3") (pin "1") (pinfunction "B_1") (pintype "passive"))
    )
    (net (code "50") (name "Net-(T3-C)") (class "Default")
      (node (ref "R22") (pin "1") (pinfunction "1_1") (pintype "passive"))
      (node (ref "T3") (pin "3") (pinfunction "C_3") (pintype "passive"))
    )
    (net (code "51") (name "Net-(T11-B)") (class "Default")
      (node (ref "R2") (pin "2") (pinfunction "2_2") (pintype "passive"))
      (node (ref "T11") (pin "1") (pinfunction "B_1") (pintype "passive"))
    )
    (net (code "52") (name "Net-(T11-C)") (class "Default")
      (node (ref "CON2") (pin "10") (pinfunction "10_10") (pintype "bidirectional"))
      (node (ref "T11") (pin "3") (pinfunction "C_3") (pintype "passive"))
    )
    (net (code "53") (name "Net-(T13-B)") (class "Default")
      (node (ref "R17") (pin "2") (pinfunction "2_2") (pintype "passive"))
      (node (ref "T13") (pin "1") (pinfunction "B_1") (pintype "passive"))
      (node (ref "T4") (pin "2") (pinfunction "E_2") (pintype "passive"))
    )
    (net (code "54") (name "Net-(T14-B)") (class "Default")
      (node (ref "R18") (pin "2") (pinfunction "2_2") (pintype "passive"))
      (node (ref "T14") (pin "1") (pinfunction "B_1") (pintype "passive"))
      (node (ref "T5") (pin "2") (pinfunction "E_2") (pintype "passive"))
    )
    (net (code "55") (name "Net-(T15-B)") (class "Default")
      (node (ref "R19") (pin "2") (pinfunction "2_2") (pintype "passive"))
      (node (ref "T15") (pin "1") (pinfunction "B_1") (pintype "passive"))
      (node (ref "T6") (pin "2") (pinfunction "E_2") (pintype "passive"))
    )
    (net (code "56") (name "Net-(T16-B)") (class "Default")
      (node (ref "R20") (pin "2") (pinfunction "2_2") (pintype "passive"))
      (node (ref "T16") (pin "1") (pinfunction "B_1") (pintype "passive"))
      (node (ref "T7") (pin "2") (pinfunction "E_2") (pintype "passive"))
    )
    (net (code "57") (name "Net-(T17-B)") (class "Default")
      (node (ref "R21") (pin "2") (pinfunction "2_2") (pintype "passive"))
      (node (ref "T17") (pin "1") (pinfunction "B_1") (pintype "passive"))
      (node (ref "T8") (pin "2") (pinfunction "E_2") (pintype "passive"))
    )
    (net (code "58") (name "Net-(T18-B)") (class "Default")
      (node (ref "R24") (pin "2") (pinfunction "2_2") (pintype "passive"))
      (node (ref "T18") (pin "1") (pinfunction "B_1") (pintype "passive"))
      (node (ref "T9") (pin "2") (pinfunction "E_2") (pintype "passive"))
    )
    (net (code "59") (name "Net-(U1-PD0(PCINT24{slash}RXD0))") (class "Default")
      (node (ref "CON5") (pin "2") (pinfunction "2_2") (pintype "bidirectional"))
      (node (ref "U1") (pin "9") (pinfunction "PD0(PCINT24/RXD0)_9") (pintype "bidirectional"))
    )
    (net (code "60") (name "Net-(U1-XTAL1)") (class "Default")
      (node (ref "C11") (pin "1") (pinfunction "1_1") (pintype "passive"))
      (node (ref "U1") (pin "8") (pinfunction "XTAL1_8") (pintype "bidirectional"))
      (node (ref "XTAL1") (pin "1") (pinfunction "1_1") (pintype "passive"))
    )
    (net (code "61") (name "Net-(U1-XTAL2)") (class "Default")
      (node (ref "C10") (pin "1") (pinfunction "1_1") (pintype "passive"))
      (node (ref "U1") (pin "7") (pinfunction "XTAL2_7") (pintype "bidirectional"))
      (node (ref "XTAL1") (pin "2") (pinfunction "2_2") (pintype "passive"))
    )
    (net (code "62") (name "Net-(U2-PROG)") (class "Default")
      (node (ref "R32") (pin "2") (pinfunction "2_2") (pintype "passive"))
      (node (ref "U2") (pin "6") (pinfunction "PROG_6") (pintype "bidirectional"))
    )
    (net (code "63") (name "Net-(U2-STAT1)") (class "Default")
      (node (ref "R1") (pin "1") (pinfunction "1_1") (pintype "passive"))
      (node (ref "U2") (pin "3") (pinfunction "STAT1_3") (pintype "bidirectional"))
    )
    (net (code "64") (name "Net-(U2-THERM)") (class "Default")
      (node (ref "R31") (pin "2") (pinfunction "2_2") (pintype "passive"))
      (node (ref "U2") (pin "8") (pinfunction "THERM_8") (pintype "bidirectional"))
    )
    (net (code "65") (name "RX1") (class "Default")
      (node (ref "R36") (pin "1") (pinfunction "1_1") (pintype "passive"))
      (node (ref "T13") (pin "3") (pinfunction "C_3") (pintype "passive"))
      (node (ref "U1") (pin "21") (pinfunction "PC2(PCINT18/TCK)_21") (pintype "bidirectional"))
    )
    (net (code "66") (name "RX2") (class "Default")
      (node (ref "R37") (pin "1") (pinfunction "1_1") (pintype "passive"))
      (node (ref "T14") (pin "3") (pinfunction "C_3") (pintype "passive"))
      (node (ref "U1") (pin "22") (pinfunction "PC3(PCINT19/TMS)_22") (pintype "bidirectional"))
    )
    (net (code "67") (name "RX3") (class "Default")
      (node (ref "R38") (pin "1") (pinfunction "1_1") (pintype "passive"))
      (node (ref "T15") (pin "3") (pinfunction "C_3") (pintype "passive"))
      (node (ref "U1") (pin "23") (pinfunction "PC4(TDO/PCINT20)_23") (pintype "bidirectional"))
    )
    (net (code "68") (name "RX4") (class "Default")
      (node (ref "R39") (pin "1") (pinfunction "1_1") (pintype "passive"))
      (node (ref "T16") (pin "3") (pinfunction "C_3") (pintype "passive"))
      (node (ref "U1") (pin "24") (pinfunction "PC5(TDI/PCINT21)_24") (pintype "bidirectional"))
    )
    (net (code "69") (name "RX5") (class "Default")
      (node (ref "R40") (pin "1") (pinfunction "1_1") (pintype "passive"))
      (node (ref "T17") (pin "3") (pinfunction "C_3") (pintype "passive"))
      (node (ref "U1") (pin "25") (pinfunction "PC6(TOSC1/PCINT22)_25") (pintype "bidirectional"))
    )
    (net (code "70") (name "RX6") (class "Default")
      (node (ref "R41") (pin "1") (pinfunction "1_1") (pintype "passive"))
      (node (ref "T18") (pin "3") (pinfunction "C_3") (pintype "passive"))
      (node (ref "U1") (pin "26") (pinfunction "PC7(TOSC2/PCINT23)_26") (pintype "bidirectional"))
    )
    (net (code "71") (name "STBY") (class "Default")
      (node (ref "U$1") (pin "19") (pinfunction "STBY_19") (pintype "bidirectional"))
      (node (ref "U1") (pin "13") (pinfunction "PD4(PCINT28/XCK1/OC1B)_13") (pintype "bidirectional"))
    )
    (net (code "72") (name "TRANSMITLEDS") (class "Default")
      (node (ref "R16") (pin "1") (pinfunction "1_1") (pintype "passive"))
      (node (ref "U1") (pin "20") (pinfunction "PC1(PCINT17/SDA)_20") (pintype "bidirectional"))
    )
    (net (code "73") (name "VSENSE") (class "Default")
      (node (ref "R29") (pin "1") (pinfunction "1_1") (pintype "passive"))
      (node (ref "R30") (pin "2") (pinfunction "2_2") (pintype "passive"))
      (node (ref "U1") (pin "37") (pinfunction "PA0(ADC0/PCINT0)_37") (pintype "bidirectional"))
    )
    (net (code "74") (name "unconnected-(CON4-Pad3)") (class "Default")
      (node (ref "CON4") (pin "3") (pinfunction "3_3") (pintype "bidirectional"))
    )
  )
)
